# SCH_rangkaianHotWheels.net
KiCad netlist of a schematic drawn in EasyEDA
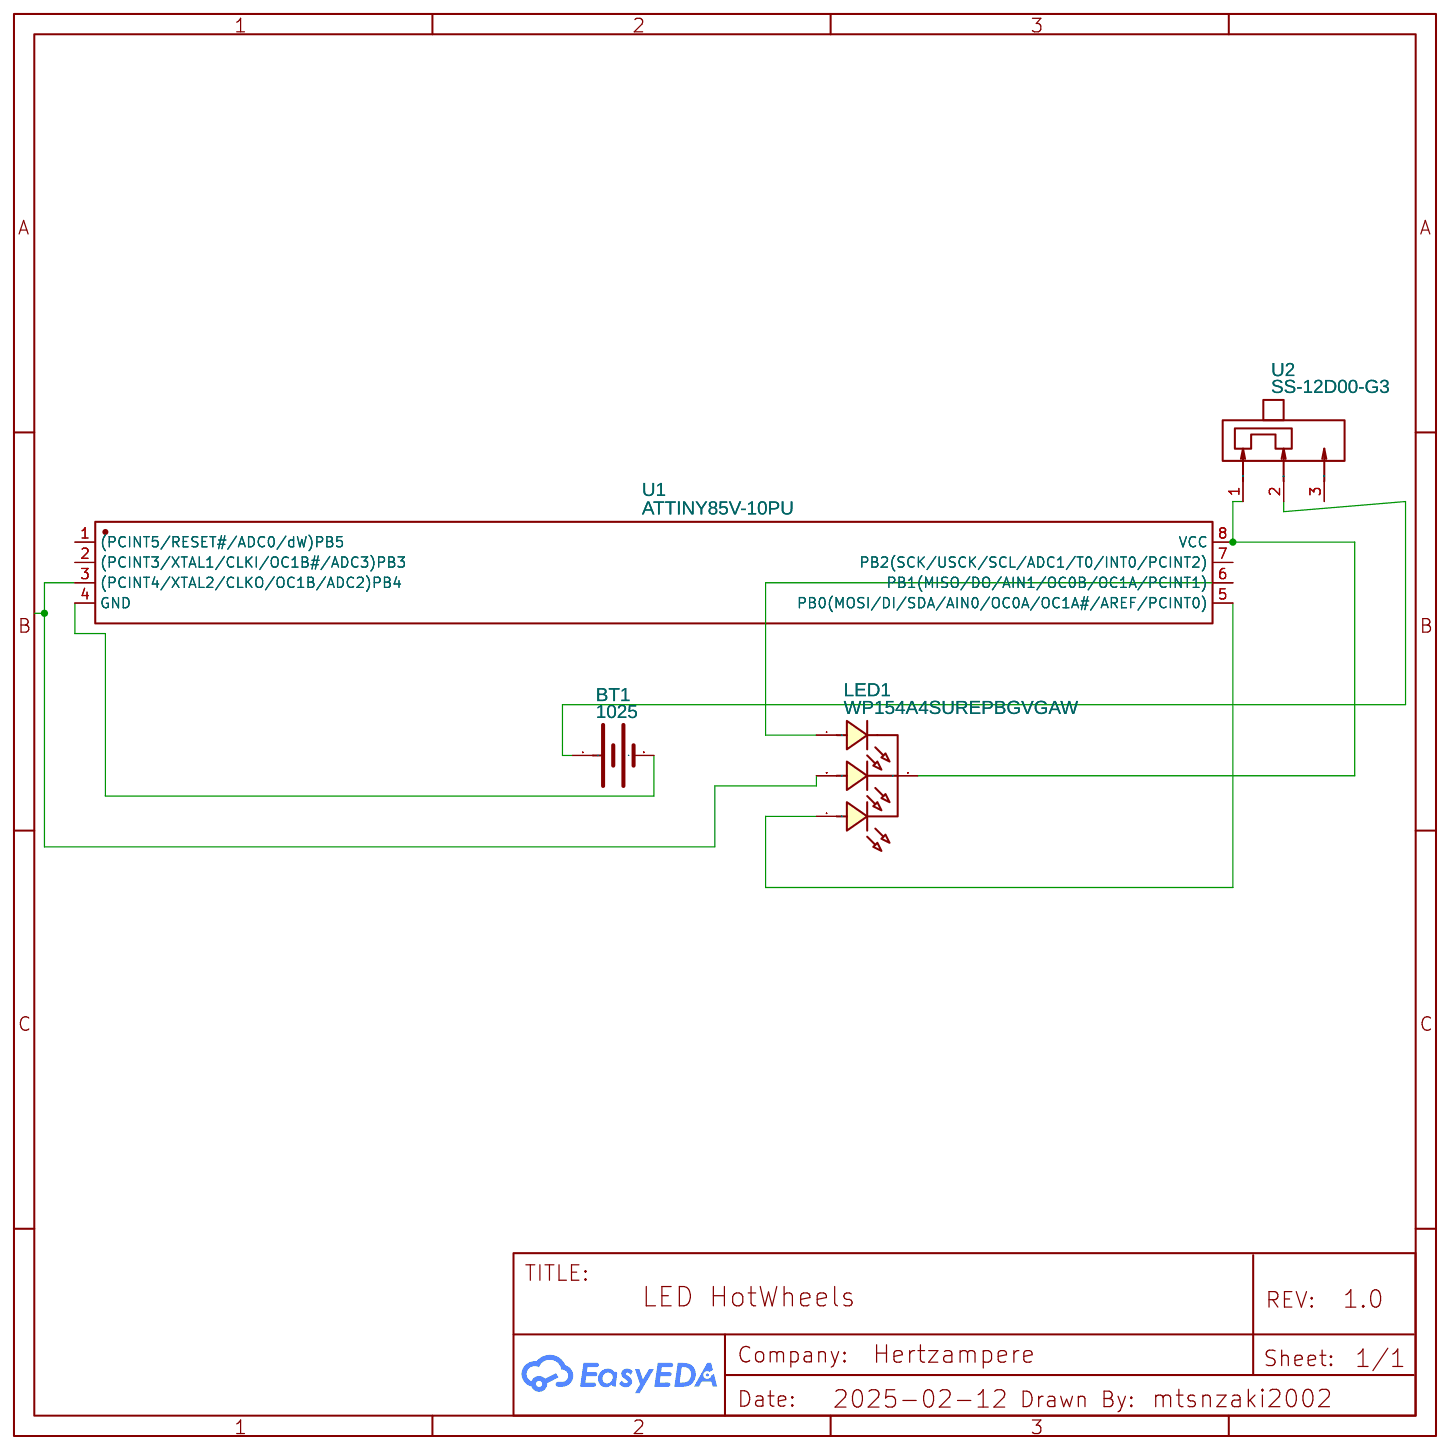
[diagram p0: schematic sheet]

(export (version "E")
  (design (tool "Eeschema 10.0.6"))
  (components
    (comp (ref "BT1")
      (value "1025")
      (fields (field (name "Manufacturer") "Keystone"))
      (libsource (lib "") (part "1025"))
    )
    (comp (ref "LED1")
      (value "WP154A4SUREPBGVGAW")
      (fields (field (name "Manufacturer") "Kingbright"))
      (libsource (lib "") (part "WP154A4SUREPBGVGAW"))
    )
    (comp (ref "U1")
      (value "ATTINY85V-10PU")
      (fields (field (name "Manufacturer") "MICROCHIP(美国微芯)"))
      (libsource (lib "") (part "ATTINY85V-10PU"))
    )
    (comp (ref "U2")
      (value "SS-12D00-G3")
      (fields (field (name "Manufacturer") "SOFNG(硕方)"))
      (libsource (lib "") (part "SS-12D00-G3"))
    )
  )
  (nets
    (net (code "1") (name "Net-(BT1-+)") (class "Default")
      (node (ref "BT1") (pin "1") (pinfunction "+_1") (pintype "passive"))
      (node (ref "U2") (pin "2") (pinfunction "2_2") (pintype "unspecified"))
    )
    (net (code "2") (name "Net-(BT1--)") (class "Default")
      (node (ref "BT1") (pin "2") (pinfunction "-_2") (pintype "passive"))
      (node (ref "U1") (pin "4") (pinfunction "GND_4") (pintype "unspecified"))
    )
    (net (code "3") (name "Net-(LED1-K)") (class "Default")
      (node (ref "LED1") (pin "2") (pinfunction "K_2") (pintype "unspecified"))
      (node (ref "U1") (pin "8") (pinfunction "VCC_8") (pintype "unspecified"))
      (node (ref "U2") (pin "1") (pinfunction "1_1") (pintype "unspecified"))
    )
    (net (code "4") (name "Net-(U1-(PCINT4{slash}XTAL2{slash}CLKO{slash}OC1B{slash}ADC2)PB4)") (class "Default")
      (node (ref "LED1") (pin "3") (pinfunction "A_3") (pintype "unspecified"))
      (node (ref "U1") (pin "3") (pinfunction "(PCINT4/XTAL2/CLKO/OC1B/ADC2)PB4_3") (pintype "unspecified"))
    )
    (net (code "5") (name "Net-(U1-PB0(MOSI{slash}DI{slash}SDA{slash}AIN0{slash}OC0A{slash}OC1A#{slash}AREF{slash}PCINT0))") (class "Default")
      (node (ref "LED1") (pin "1") (pinfunction "A_1") (pintype "unspecified"))
      (node (ref "U1") (pin "5") (pinfunction "PB0(MOSI/DI/SDA/AIN0/OC0A/OC1A#/AREF/PCINT0)_5") (pintype "unspecified"))
    )
    (net (code "6") (name "Net-(U1-PB1(MISO{slash}DO{slash}AIN1{slash}OC0B{slash}OC1A{slash}PCINT1))") (class "Default")
      (node (ref "LED1") (pin "4") (pinfunction "A_4") (pintype "unspecified"))
      (node (ref "U1") (pin "6") (pinfunction "PB1(MISO/DO/AIN1/OC0B/OC1A/PCINT1)_6") (pintype "unspecified"))
    )
    (net (code "7") (name "unconnected-(U1-(PCINT3{slash}XTAL1{slash}CLKI{slash}OC1B#{slash}ADC3)PB3-Pad2)") (class "Default")
      (node (ref "U1") (pin "2") (pinfunction "(PCINT3/XTAL1/CLKI/OC1B#/ADC3)PB3_2") (pintype "unspecified"))
    )
    (net (code "8") (name "unconnected-(U1-(PCINT5{slash}RESET#{slash}ADC0{slash}dW)PB5-Pad1)") (class "Default")
      (node (ref "U1") (pin "1") (pinfunction "(PCINT5/RESET#/ADC0/dW)PB5_1") (pintype "unspecified"))
    )
    (net (code "9") (name "unconnected-(U1-PB2(SCK{slash}USCK{slash}SCL{slash}ADC1{slash}T0{slash}INT0{slash}PCINT2)-Pad7)") (class "Default")
      (node (ref "U1") (pin "7") (pinfunction "PB2(SCK/USCK/SCL/ADC1/T0/INT0/PCINT2)_7") (pintype "unspecified"))
    )
    (net (code "10") (name "unconnected-(U2-Pad3)") (class "Default")
      (node (ref "U2") (pin "3") (pinfunction "3_3") (pintype "unspecified"))
    )
  )
)
